# Petra_2.net
KiCad netlist of a schematic drawn in EAGLE
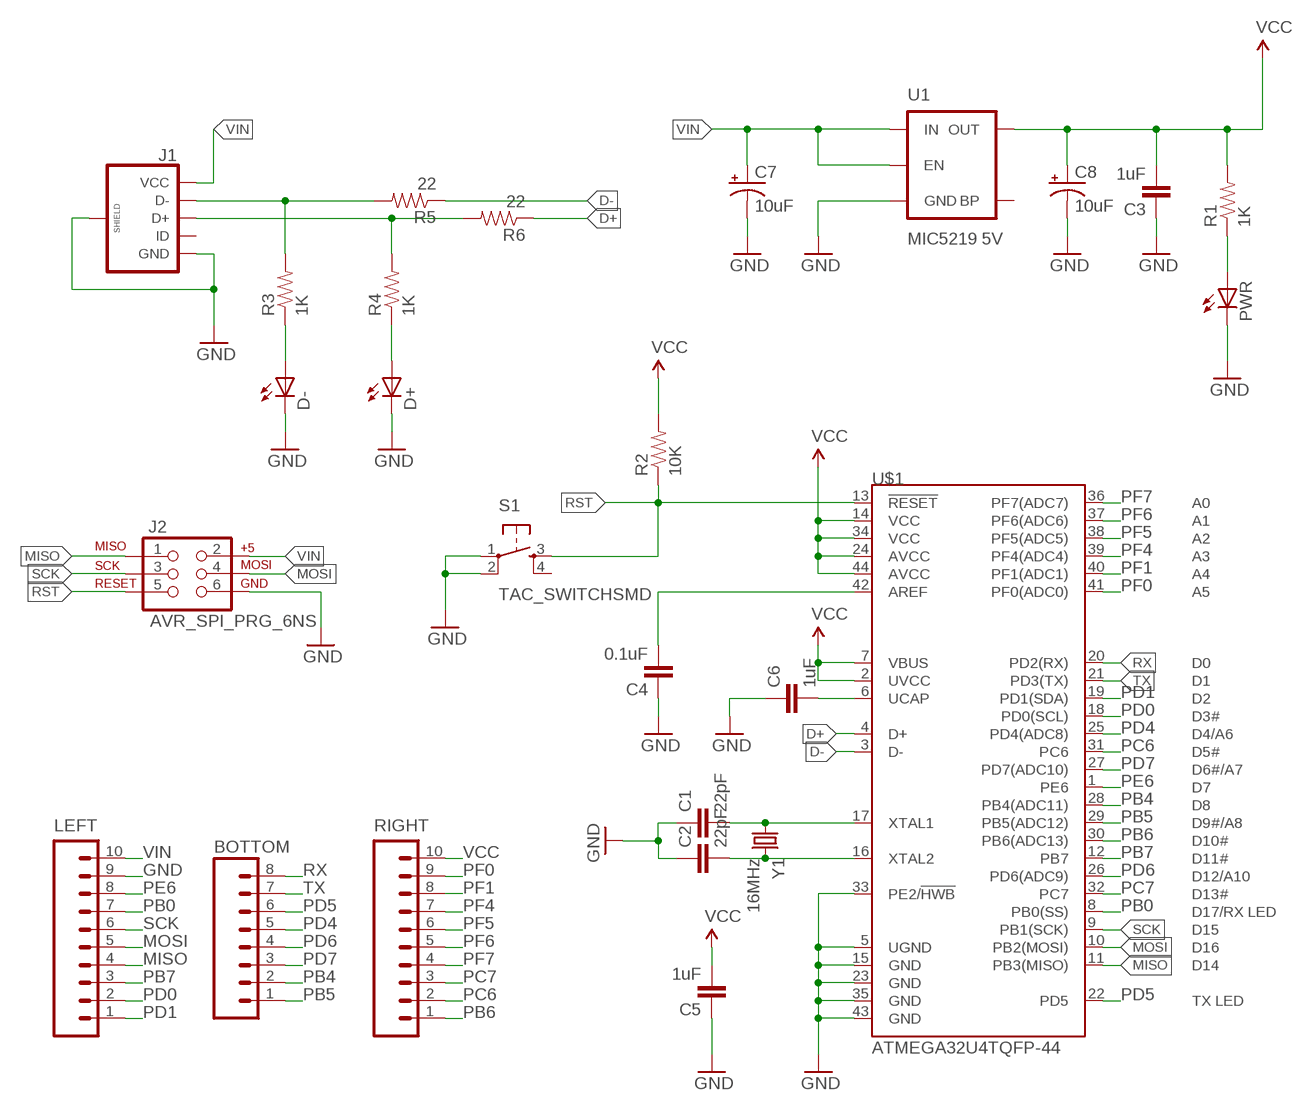
[diagram p0: schematic, sheet 1]

(export (version "E")
  (design (tool "Eeschema 10.0.6"))
  (components
    (comp (ref "BOTTOM")
      (value "M08")
      (footprint "eagle-import:1X08_ROUND")
      (libsource (lib "eagle-import") (part "M08"))
    )
    (comp (ref "C1")
      (value "22pF")
      (footprint "eagle-import:0402-CAP")
      (libsource (lib "eagle-import") (part "CAP0402-CAP"))
    )
    (comp (ref "C2")
      (value "22pF")
      (footprint "eagle-import:0402-CAP")
      (libsource (lib "eagle-import") (part "CAP0402-CAP"))
    )
    (comp (ref "C3")
      (value "1uF")
      (footprint "eagle-import:0402-CAP")
      (libsource (lib "eagle-import") (part "CAP0402-CAP"))
    )
    (comp (ref "C4")
      (value "0.1uF")
      (footprint "eagle-import:0402-CAP")
      (libsource (lib "eagle-import") (part "CAP0402-CAP"))
    )
    (comp (ref "C5")
      (value "1uF")
      (footprint "eagle-import:0402-CAP")
      (libsource (lib "eagle-import") (part "CAP0402-CAP"))
    )
    (comp (ref "C6")
      (value "1uF")
      (footprint "eagle-import:0402-CAP")
      (libsource (lib "eagle-import") (part "CAP0402-CAP"))
    )
    (comp (ref "C7")
      (value "10uF")
      (footprint "eagle-import:EIA3216")
      (libsource (lib "eagle-import") (part "CAP_POL1206"))
    )
    (comp (ref "C8")
      (value "10uF")
      (footprint "eagle-import:EIA3216")
      (libsource (lib "eagle-import") (part "CAP_POL1206"))
    )
    (comp (ref "D+")
      (value "LEDCHIP-LED0805")
      (footprint "eagle-import:CHIP-LED0805")
      (libsource (lib "eagle-import") (part "LEDCHIP-LED0805"))
    )
    (comp (ref "D-")
      (value "LEDCHIP-LED0805")
      (footprint "eagle-import:CHIP-LED0805")
      (libsource (lib "eagle-import") (part "LEDCHIP-LED0805"))
    )
    (comp (ref "J1")
      (value "USB_MICROB_PLUGCONN-11752")
      (footprint "eagle-import:USB-B-MICRO-SMD_V03")
      (libsource (lib "eagle-import") (part "USB_MICROB_PLUGCONN-11752"))
    )
    (comp (ref "J2")
      (value "AVR_SPI_PRG_6NS")
      (footprint "eagle-import:2X3-NS")
      (libsource (lib "eagle-import") (part "AVR_SPI_PRG_6NS"))
    )
    (comp (ref "LEFT")
      (value "M10SILK_FEMALE_PTH")
      (footprint "eagle-import:1X10")
      (libsource (lib "eagle-import") (part "M10SILK_FEMALE_PTH"))
    )
    (comp (ref "PWR")
      (value "LEDCHIP-LED0805")
      (footprint "eagle-import:CHIP-LED0805")
      (libsource (lib "eagle-import") (part "LEDCHIP-LED0805"))
    )
    (comp (ref "R1")
      (value "1K")
      (footprint "eagle-import:0603-RES")
      (libsource (lib "eagle-import") (part "10KOHM-1/10W-1%(0603)0603"))
    )
    (comp (ref "R2")
      (value "10K")
      (footprint "eagle-import:0603-RES")
      (libsource (lib "eagle-import") (part "10KOHM-1/10W-1%(0603)0603"))
    )
    (comp (ref "R3")
      (value "1K")
      (footprint "eagle-import:0603-RES")
      (libsource (lib "eagle-import") (part "10KOHM-1/10W-1%(0603)0603"))
    )
    (comp (ref "R4")
      (value "1K")
      (footprint "eagle-import:0603-RES")
      (libsource (lib "eagle-import") (part "10KOHM-1/10W-1%(0603)0603"))
    )
    (comp (ref "R5")
      (value "22")
      (footprint "eagle-import:0603-RES")
      (libsource (lib "eagle-import") (part "10KOHM-1/10W-1%(0603)0603"))
    )
    (comp (ref "R6")
      (value "22")
      (footprint "eagle-import:0603-RES")
      (libsource (lib "eagle-import") (part "10KOHM-1/10W-1%(0603)0603"))
    )
    (comp (ref "RIGHT")
      (value "M10SILK_FEMALE_PTH")
      (footprint "eagle-import:1X10")
      (libsource (lib "eagle-import") (part "M10SILK_FEMALE_PTH"))
    )
    (comp (ref "S1")
      (value "TAC_SWITCHSMD")
      (footprint "eagle-import:TACTILE-SWITCH-SMD")
      (libsource (lib "eagle-import") (part "TAC_SWITCHSMD"))
    )
    (comp (ref "U$1")
      (value "ATMEGA32U4TQFP-44")
      (footprint "eagle-import:TQFP44")
      (libsource (lib "eagle-import") (part "ATMEGA32U4TQFP-44"))
    )
    (comp (ref "U1")
      (value "MIC5219 5V")
      (footprint "eagle-import:SOT23-5")
      (libsource (lib "eagle-import") (part "V_REG_MIC52195V"))
    )
    (comp (ref "Y1")
      (value "16MHz")
      (footprint "eagle-import:CRYSTAL-SMD-5X3")
      (libsource (lib "eagle-import") (part "CRYSTALCRYSTAL-SMD-5X3-16MHZ"))
    )
  )
  (nets
    (net (code "1") (name "/PB0") (class "Default")
      (node (ref "LEFT") (pin "7") (pinfunction "7_7") (pintype "passive"))
      (node (ref "U$1") (pin "8") (pinfunction "PB0(SS)_8") (pintype "bidirectional"))
    )
    (net (code "2") (name "/PB4") (class "Default")
      (node (ref "BOTTOM") (pin "2") (pinfunction "2_2") (pintype "passive"))
      (node (ref "U$1") (pin "28") (pinfunction "PB4(ADC11)_28") (pintype "bidirectional"))
    )
    (net (code "3") (name "/PB5") (class "Default")
      (node (ref "BOTTOM") (pin "1") (pinfunction "1_1") (pintype "passive"))
      (node (ref "U$1") (pin "29") (pinfunction "PB5(ADC12)_29") (pintype "bidirectional"))
    )
    (net (code "4") (name "/PB6") (class "Default")
      (node (ref "RIGHT") (pin "1") (pinfunction "1_1") (pintype "passive"))
      (node (ref "U$1") (pin "30") (pinfunction "PB6(ADC13)_30") (pintype "bidirectional"))
    )
    (net (code "5") (name "/PB7") (class "Default")
      (node (ref "LEFT") (pin "3") (pinfunction "3_3") (pintype "passive"))
      (node (ref "U$1") (pin "12") (pinfunction "PB7_12") (pintype "bidirectional"))
    )
    (net (code "6") (name "/PC6") (class "Default")
      (node (ref "RIGHT") (pin "2") (pinfunction "2_2") (pintype "passive"))
      (node (ref "U$1") (pin "31") (pinfunction "PC6_31") (pintype "bidirectional"))
    )
    (net (code "7") (name "/PC7") (class "Default")
      (node (ref "RIGHT") (pin "3") (pinfunction "3_3") (pintype "passive"))
      (node (ref "U$1") (pin "32") (pinfunction "PC7_32") (pintype "bidirectional"))
    )
    (net (code "8") (name "/PD0") (class "Default")
      (node (ref "LEFT") (pin "2") (pinfunction "2_2") (pintype "passive"))
      (node (ref "U$1") (pin "18") (pinfunction "PD0(SCL)_18") (pintype "bidirectional"))
    )
    (net (code "9") (name "/PD1") (class "Default")
      (node (ref "LEFT") (pin "1") (pinfunction "1_1") (pintype "passive"))
      (node (ref "U$1") (pin "19") (pinfunction "PD1(SDA)_19") (pintype "bidirectional"))
    )
    (net (code "10") (name "/PD4") (class "Default")
      (node (ref "BOTTOM") (pin "5") (pinfunction "5_5") (pintype "passive"))
      (node (ref "U$1") (pin "25") (pinfunction "PD4(ADC8)_25") (pintype "bidirectional"))
    )
    (net (code "11") (name "/PD5") (class "Default")
      (node (ref "BOTTOM") (pin "6") (pinfunction "6_6") (pintype "passive"))
      (node (ref "U$1") (pin "22") (pinfunction "PD5_22") (pintype "bidirectional"))
    )
    (net (code "12") (name "/PD6") (class "Default")
      (node (ref "BOTTOM") (pin "4") (pinfunction "4_4") (pintype "passive"))
      (node (ref "U$1") (pin "26") (pinfunction "PD6(ADC9)_26") (pintype "bidirectional"))
    )
    (net (code "13") (name "/PD7") (class "Default")
      (node (ref "BOTTOM") (pin "3") (pinfunction "3_3") (pintype "passive"))
      (node (ref "U$1") (pin "27") (pinfunction "PD7(ADC10)_27") (pintype "bidirectional"))
    )
    (net (code "14") (name "/PE6") (class "Default")
      (node (ref "LEFT") (pin "8") (pinfunction "8_8") (pintype "passive"))
      (node (ref "U$1") (pin "1") (pinfunction "PE6_1") (pintype "bidirectional"))
    )
    (net (code "15") (name "/PF0") (class "Default")
      (node (ref "RIGHT") (pin "9") (pinfunction "9_9") (pintype "passive"))
      (node (ref "U$1") (pin "41") (pinfunction "PF0(ADC0)_41") (pintype "bidirectional"))
    )
    (net (code "16") (name "/PF1") (class "Default")
      (node (ref "RIGHT") (pin "8") (pinfunction "8_8") (pintype "passive"))
      (node (ref "U$1") (pin "40") (pinfunction "PF1(ADC1)_40") (pintype "bidirectional"))
    )
    (net (code "17") (name "/PF4") (class "Default")
      (node (ref "RIGHT") (pin "7") (pinfunction "7_7") (pintype "passive"))
      (node (ref "U$1") (pin "39") (pinfunction "PF4(ADC4)_39") (pintype "bidirectional"))
    )
    (net (code "18") (name "/PF5") (class "Default")
      (node (ref "RIGHT") (pin "6") (pinfunction "6_6") (pintype "passive"))
      (node (ref "U$1") (pin "38") (pinfunction "PF5(ADC5)_38") (pintype "bidirectional"))
    )
    (net (code "19") (name "/PF6") (class "Default")
      (node (ref "RIGHT") (pin "5") (pinfunction "5_5") (pintype "passive"))
      (node (ref "U$1") (pin "37") (pinfunction "PF6(ADC6)_37") (pintype "bidirectional"))
    )
    (net (code "20") (name "/PF7") (class "Default")
      (node (ref "RIGHT") (pin "4") (pinfunction "4_4") (pintype "passive"))
      (node (ref "U$1") (pin "36") (pinfunction "PF7(ADC7)_36") (pintype "bidirectional"))
    )
    (net (code "21") (name "D+") (class "Default")
      (node (ref "R6") (pin "1") (pinfunction "1_1") (pintype "passive"))
      (node (ref "U$1") (pin "4") (pinfunction "D+_4") (pintype "bidirectional"))
    )
    (net (code "22") (name "D-") (class "Default")
      (node (ref "R5") (pin "1") (pinfunction "1_1") (pintype "passive"))
      (node (ref "U$1") (pin "3") (pinfunction "D-_3") (pintype "bidirectional"))
    )
    (net (code "23") (name "GND") (class "Default")
      (node (ref "C1") (pin "1") (pinfunction "1_1") (pintype "passive"))
      (node (ref "C2") (pin "1") (pinfunction "1_1") (pintype "passive"))
      (node (ref "C3") (pin "1") (pinfunction "1_1") (pintype "passive"))
      (node (ref "C4") (pin "1") (pinfunction "1_1") (pintype "passive"))
      (node (ref "C5") (pin "1") (pinfunction "1_1") (pintype "passive"))
      (node (ref "C6") (pin "1") (pinfunction "1_1") (pintype "passive"))
      (node (ref "C7") (pin "C") (pinfunction "-_C") (pintype "passive"))
      (node (ref "C8") (pin "C") (pinfunction "-_C") (pintype "passive"))
      (node (ref "D+") (pin "C") (pinfunction "C_C") (pintype "passive"))
      (node (ref "D-") (pin "C") (pinfunction "C_C") (pintype "passive"))
      (node (ref "J1") (pin "GND") (pinfunction "GND_GND") (pintype "bidirectional"))
      (node (ref "J1") (pin "SHIELD1") (pinfunction "SHIELD_SHIELD1") (pintype "bidirectional"))
      (node (ref "J1") (pin "SHIELD2") (pinfunction "SHIELD_SHIELD2") (pintype "bidirectional"))
      (node (ref "J1") (pin "SHIELD3") (pinfunction "SHIELD_SHIELD3") (pintype "bidirectional"))
      (node (ref "J2") (pin "6") (pinfunction "6_6") (pintype "passive"))
      (node (ref "LEFT") (pin "9") (pinfunction "9_9") (pintype "passive"))
      (node (ref "PWR") (pin "C") (pinfunction "C_C") (pintype "passive"))
      (node (ref "S1") (pin "1") (pinfunction "1_1") (pintype "passive"))
      (node (ref "S1") (pin "2") (pinfunction "2_2") (pintype "passive"))
      (node (ref "U$1") (pin "15") (pinfunction "GND_15") (pintype "bidirectional"))
      (node (ref "U$1") (pin "23") (pinfunction "GND_23") (pintype "bidirectional"))
      (node (ref "U$1") (pin "33") (pinfunction "PE2/~{HWB}_33") (pintype "bidirectional"))
      (node (ref "U$1") (pin "35") (pinfunction "GND_35") (pintype "bidirectional"))
      (node (ref "U$1") (pin "43") (pinfunction "GND_43") (pintype "bidirectional"))
      (node (ref "U$1") (pin "5") (pinfunction "UGND_5") (pintype "bidirectional"))
      (node (ref "U1") (pin "2") (pinfunction "GND_2") (pintype "input"))
    )
    (net (code "24") (name "MISO") (class "Default")
      (node (ref "J2") (pin "1") (pinfunction "1_1") (pintype "passive"))
      (node (ref "LEFT") (pin "4") (pinfunction "4_4") (pintype "passive"))
      (node (ref "U$1") (pin "11") (pinfunction "PB3(MISO)_11") (pintype "bidirectional"))
    )
    (net (code "25") (name "MOSI") (class "Default")
      (node (ref "J2") (pin "4") (pinfunction "4_4") (pintype "passive"))
      (node (ref "LEFT") (pin "5") (pinfunction "5_5") (pintype "passive"))
      (node (ref "U$1") (pin "10") (pinfunction "PB2(MOSI)_10") (pintype "bidirectional"))
    )
    (net (code "26") (name "Net-(D+-PadA)") (class "Default")
      (node (ref "D+") (pin "A") (pinfunction "A_A") (pintype "passive"))
      (node (ref "R4") (pin "1") (pinfunction "1_1") (pintype "passive"))
    )
    (net (code "27") (name "Net-(D--PadA)") (class "Default")
      (node (ref "D-") (pin "A") (pinfunction "A_A") (pintype "passive"))
      (node (ref "R3") (pin "1") (pinfunction "1_1") (pintype "passive"))
    )
    (net (code "28") (name "Net-(J1-PadD+)") (class "Default")
      (node (ref "J1") (pin "D+") (pinfunction "D+_D+") (pintype "bidirectional"))
      (node (ref "R4") (pin "2") (pinfunction "2_2") (pintype "passive"))
      (node (ref "R6") (pin "2") (pinfunction "2_2") (pintype "passive"))
    )
    (net (code "29") (name "Net-(J1-PadD-)") (class "Default")
      (node (ref "J1") (pin "D-") (pinfunction "D-_D-") (pintype "bidirectional"))
      (node (ref "R3") (pin "2") (pinfunction "2_2") (pintype "passive"))
      (node (ref "R5") (pin "2") (pinfunction "2_2") (pintype "passive"))
    )
    (net (code "30") (name "Net-(PWR-PadA)") (class "Default")
      (node (ref "PWR") (pin "A") (pinfunction "A_A") (pintype "passive"))
      (node (ref "R1") (pin "1") (pinfunction "1_1") (pintype "passive"))
    )
    (net (code "31") (name "Net-(U$1-AREF)") (class "Default")
      (node (ref "C4") (pin "2") (pinfunction "2_2") (pintype "passive"))
      (node (ref "U$1") (pin "42") (pinfunction "AREF_42") (pintype "bidirectional"))
    )
    (net (code "32") (name "Net-(U$1-UCAP)") (class "Default")
      (node (ref "C6") (pin "2") (pinfunction "2_2") (pintype "passive"))
      (node (ref "U$1") (pin "6") (pinfunction "UCAP_6") (pintype "bidirectional"))
    )
    (net (code "33") (name "Net-(U$1-XTAL1)") (class "Default")
      (node (ref "C1") (pin "2") (pinfunction "2_2") (pintype "passive"))
      (node (ref "U$1") (pin "17") (pinfunction "XTAL1_17") (pintype "bidirectional"))
      (node (ref "Y1") (pin "1") (pinfunction "1_1") (pintype "passive"))
    )
    (net (code "34") (name "Net-(U$1-XTAL2)") (class "Default")
      (node (ref "C2") (pin "2") (pinfunction "2_2") (pintype "passive"))
      (node (ref "U$1") (pin "16") (pinfunction "XTAL2_16") (pintype "bidirectional"))
      (node (ref "Y1") (pin "3") (pinfunction "2_3") (pintype "passive"))
    )
    (net (code "35") (name "RST") (class "Default")
      (node (ref "J2") (pin "5") (pinfunction "5_5") (pintype "passive"))
      (node (ref "R2") (pin "1") (pinfunction "1_1") (pintype "passive"))
      (node (ref "S1") (pin "3") (pinfunction "3_3") (pintype "passive"))
      (node (ref "U$1") (pin "13") (pinfunction "~{RESET}_13") (pintype "bidirectional"))
    )
    (net (code "36") (name "RX") (class "Default")
      (node (ref "BOTTOM") (pin "8") (pinfunction "8_8") (pintype "passive"))
      (node (ref "U$1") (pin "20") (pinfunction "PD2(RX)_20") (pintype "bidirectional"))
    )
    (net (code "37") (name "SCK") (class "Default")
      (node (ref "J2") (pin "3") (pinfunction "3_3") (pintype "passive"))
      (node (ref "LEFT") (pin "6") (pinfunction "6_6") (pintype "passive"))
      (node (ref "U$1") (pin "9") (pinfunction "PB1(SCK)_9") (pintype "bidirectional"))
    )
    (net (code "38") (name "TX") (class "Default")
      (node (ref "BOTTOM") (pin "7") (pinfunction "7_7") (pintype "passive"))
      (node (ref "U$1") (pin "21") (pinfunction "PD3(TX)_21") (pintype "bidirectional"))
    )
    (net (code "39") (name "VCC") (class "Default")
      (node (ref "C3") (pin "2") (pinfunction "2_2") (pintype "passive"))
      (node (ref "C5") (pin "2") (pinfunction "2_2") (pintype "passive"))
      (node (ref "C8") (pin "A") (pinfunction "+_A") (pintype "passive"))
      (node (ref "R1") (pin "2") (pinfunction "2_2") (pintype "passive"))
      (node (ref "R2") (pin "2") (pinfunction "2_2") (pintype "passive"))
      (node (ref "RIGHT") (pin "10") (pinfunction "10_10") (pintype "passive"))
      (node (ref "U$1") (pin "14") (pinfunction "VCC_14") (pintype "bidirectional"))
      (node (ref "U$1") (pin "2") (pinfunction "UVCC_2") (pintype "bidirectional"))
      (node (ref "U$1") (pin "24") (pinfunction "AVCC_24") (pintype "bidirectional"))
      (node (ref "U$1") (pin "34") (pinfunction "VCC_34") (pintype "bidirectional"))
      (node (ref "U$1") (pin "44") (pinfunction "AVCC_44") (pintype "bidirectional"))
      (node (ref "U$1") (pin "7") (pinfunction "VBUS_7") (pintype "bidirectional"))
      (node (ref "U1") (pin "5") (pinfunction "OUT_5") (pintype "passive"))
    )
    (net (code "40") (name "VIN") (class "Default")
      (node (ref "C7") (pin "A") (pinfunction "+_A") (pintype "passive"))
      (node (ref "J1") (pin "VBUS") (pinfunction "VCC_VBUS") (pintype "bidirectional"))
      (node (ref "J2") (pin "2") (pinfunction "2_2") (pintype "passive"))
      (node (ref "LEFT") (pin "10") (pinfunction "10_10") (pintype "passive"))
      (node (ref "U1") (pin "1") (pinfunction "IN_1") (pintype "input"))
      (node (ref "U1") (pin "3") (pinfunction "EN_3") (pintype "input"))
    )
    (net (code "41") (name "unconnected-(J1-PadID)") (class "Default")
      (node (ref "J1") (pin "ID") (pinfunction "ID_ID") (pintype "bidirectional"))
    )
    (net (code "42") (name "unconnected-(S1-Pad4)") (class "Default")
      (node (ref "S1") (pin "4") (pinfunction "4_4") (pintype "passive"))
    )
    (net (code "43") (name "unconnected-(U1-BP-Pad4)") (class "Default")
      (node (ref "U1") (pin "4") (pinfunction "BP_4") (pintype "input"))
    )
  )
)
